# Sheet2.net
KiCad netlist of a schematic drawn in Altium Designer
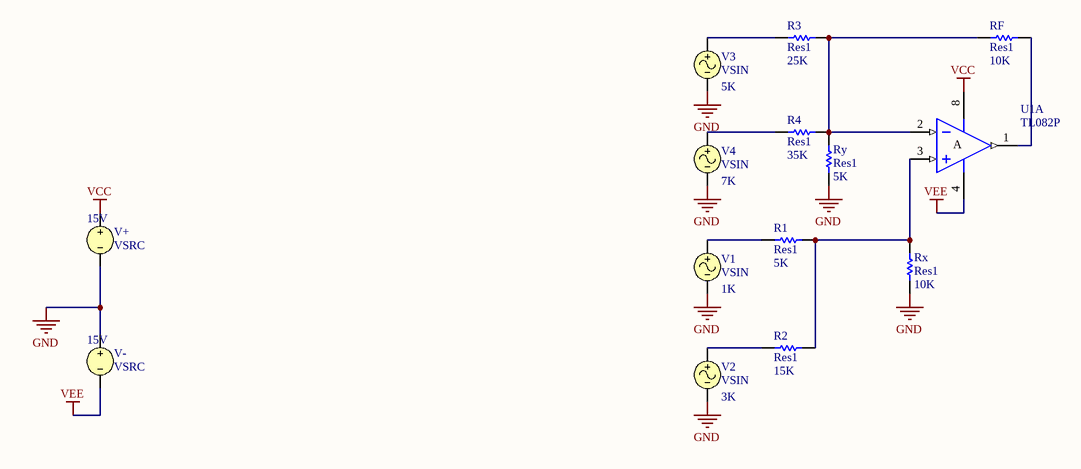
[diagram p0: Sheet2.SchDoc]

(export (version "E")
  (design (tool "Eeschema 10.0.6"))
  (components
    (comp (ref "R1")
      (value "Res1")
      (footprint "AXIAL-0.3")
      (description "Resistor")
      (fields (field (name "ALTIUM_VALUE") "5K") (field (name "PUBLISHER") "Altium Limited"))
      (libsource (lib "Miscellaneous Devices") (part "Res1"))
    )
    (comp (ref "R2")
      (value "Res1")
      (footprint "AXIAL-0.3")
      (description "Resistor")
      (fields (field (name "ALTIUM_VALUE") "15K") (field (name "PUBLISHER") "Altium Limited"))
      (libsource (lib "Miscellaneous Devices") (part "Res1"))
    )
    (comp (ref "R3")
      (value "Res1")
      (footprint "AXIAL-0.3")
      (description "Resistor")
      (fields (field (name "ALTIUM_VALUE") "25K") (field (name "PUBLISHER") "Altium Limited"))
      (libsource (lib "Miscellaneous Devices") (part "Res1"))
    )
    (comp (ref "R4")
      (value "Res1")
      (footprint "AXIAL-0.3")
      (description "Resistor")
      (fields (field (name "ALTIUM_VALUE") "35K") (field (name "PUBLISHER") "Altium Limited"))
      (libsource (lib "Miscellaneous Devices") (part "Res1"))
    )
    (comp (ref "RF")
      (value "Res1")
      (footprint "AXIAL-0.3")
      (description "Resistor")
      (fields (field (name "ALTIUM_VALUE") "10K") (field (name "PUBLISHER") "Altium Limited"))
      (libsource (lib "Miscellaneous Devices") (part "Res1"))
    )
    (comp (ref "Rx")
      (value "Res1")
      (footprint "AXIAL-0.3")
      (description "Resistor")
      (fields (field (name "ALTIUM_VALUE") "10K") (field (name "PUBLISHER") "Altium Limited"))
      (libsource (lib "Miscellaneous Devices") (part "Res1"))
    )
    (comp (ref "Ry")
      (value "Res1")
      (footprint "AXIAL-0.3")
      (description "Resistor")
      (fields (field (name "ALTIUM_VALUE") "5K") (field (name "PUBLISHER") "Altium Limited"))
      (libsource (lib "Miscellaneous Devices") (part "Res1"))
    )
    (comp (ref "U1")
      (value "TL082P")
      (footprint "P008")
      (description "JFET-Input Operational Amplifier")
      (fields (field (name "PUBLISHER") "Altium Limited"))
      (libsource (lib "TI Operational Amplifier") (part "TL082P"))
    )
    (comp (ref "V+")
      (value "VSRC")
      (description "Voltage Source")
      (fields (field (name "ALTIUM_VALUE") "15V") (field (name "PUBLISHER") "Altium Limited"))
      (libsource (lib "Simulation Sources") (part "VSRC"))
    )
    (comp (ref "V-")
      (value "VSRC")
      (description "Voltage Source")
      (fields (field (name "ALTIUM_VALUE") "15V") (field (name "PUBLISHER") "Altium Limited"))
      (libsource (lib "Simulation Sources") (part "VSRC"))
    )
    (comp (ref "V1")
      (value "VSIN")
      (description "Sinusoidal Voltage Source")
      (fields (field (name "FREQUENCY") "1K") (field (name "PUBLISHER") "Altium Limited"))
      (libsource (lib "Simulation Sources") (part "VSIN"))
    )
    (comp (ref "V2")
      (value "VSIN")
      (description "Sinusoidal Voltage Source")
      (fields (field (name "FREQUENCY") "3K") (field (name "PUBLISHER") "Altium Limited"))
      (libsource (lib "Simulation Sources") (part "VSIN"))
    )
    (comp (ref "V3")
      (value "VSIN")
      (description "Sinusoidal Voltage Source")
      (fields (field (name "FREQUENCY") "5K") (field (name "PUBLISHER") "Altium Limited"))
      (libsource (lib "Simulation Sources") (part "VSIN"))
    )
    (comp (ref "V4")
      (value "VSIN")
      (description "Sinusoidal Voltage Source")
      (fields (field (name "FREQUENCY") "7K") (field (name "PUBLISHER") "Altium Limited"))
      (libsource (lib "Simulation Sources") (part "VSIN"))
    )
  )
  (nets
    (net (code "1") (name "GND") (class "Default")
      (node (ref "Rx") (pin "1") (pinfunction "1_1") (pintype "passive"))
      (node (ref "Ry") (pin "1") (pinfunction "1_1") (pintype "passive"))
      (node (ref "V+") (pin "2") (pinfunction "2_2") (pintype "passive"))
      (node (ref "V-") (pin "1") (pinfunction "1_1") (pintype "passive"))
      (node (ref "V1") (pin "2") (pinfunction "2_2") (pintype "passive"))
      (node (ref "V2") (pin "2") (pinfunction "2_2") (pintype "passive"))
      (node (ref "V3") (pin "2") (pinfunction "2_2") (pintype "passive"))
      (node (ref "V4") (pin "2") (pinfunction "2_2") (pintype "passive"))
    )
    (net (code "2") (name "Net-(R1-Pad1)") (class "Default")
      (node (ref "R1") (pin "1") (pinfunction "1_1") (pintype "passive"))
      (node (ref "V1") (pin "1") (pinfunction "1_1") (pintype "passive"))
    )
    (net (code "3") (name "Net-(R2-Pad1)") (class "Default")
      (node (ref "R2") (pin "1") (pinfunction "1_1") (pintype "passive"))
      (node (ref "V2") (pin "1") (pinfunction "1_1") (pintype "passive"))
    )
    (net (code "4") (name "Net-(R3-Pad1)") (class "Default")
      (node (ref "R3") (pin "1") (pinfunction "1_1") (pintype "passive"))
      (node (ref "V3") (pin "1") (pinfunction "1_1") (pintype "passive"))
    )
    (net (code "5") (name "Net-(R4-Pad1)") (class "Default")
      (node (ref "R4") (pin "1") (pinfunction "1_1") (pintype "passive"))
      (node (ref "V4") (pin "1") (pinfunction "1_1") (pintype "passive"))
    )
    (net (code "6") (name "Net-(U1A-IN+)") (class "Default")
      (node (ref "R1") (pin "2") (pinfunction "2_2") (pintype "passive"))
      (node (ref "R2") (pin "2") (pinfunction "2_2") (pintype "passive"))
      (node (ref "Rx") (pin "2") (pinfunction "2_2") (pintype "passive"))
      (node (ref "U1") (pin "3") (pinfunction "IN+_3") (pintype "input"))
    )
    (net (code "7") (name "Net-(U1A-IN-)") (class "Default")
      (node (ref "R3") (pin "2") (pinfunction "2_2") (pintype "passive"))
      (node (ref "R4") (pin "2") (pinfunction "2_2") (pintype "passive"))
      (node (ref "RF") (pin "1") (pinfunction "1_1") (pintype "passive"))
      (node (ref "Ry") (pin "2") (pinfunction "2_2") (pintype "passive"))
      (node (ref "U1") (pin "2") (pinfunction "IN-_2") (pintype "input"))
    )
    (net (code "8") (name "Net-(U1A-OUT)") (class "Default")
      (node (ref "RF") (pin "2") (pinfunction "2_2") (pintype "passive"))
      (node (ref "U1") (pin "1") (pinfunction "OUT_1") (pintype "output"))
    )
    (net (code "9") (name "VCC") (class "Default")
      (node (ref "U1") (pin "8") (pinfunction "V+_8") (pintype "power_in"))
      (node (ref "V+") (pin "1") (pinfunction "1_1") (pintype "passive"))
    )
    (net (code "10") (name "VEE") (class "Default")
      (node (ref "U1") (pin "4") (pinfunction "V-_4") (pintype "power_in"))
      (node (ref "V-") (pin "2") (pinfunction "2_2") (pintype "passive"))
    )
  )
)
